# MPU-6050.net
KiCad netlist of a schematic drawn in Altium Designer
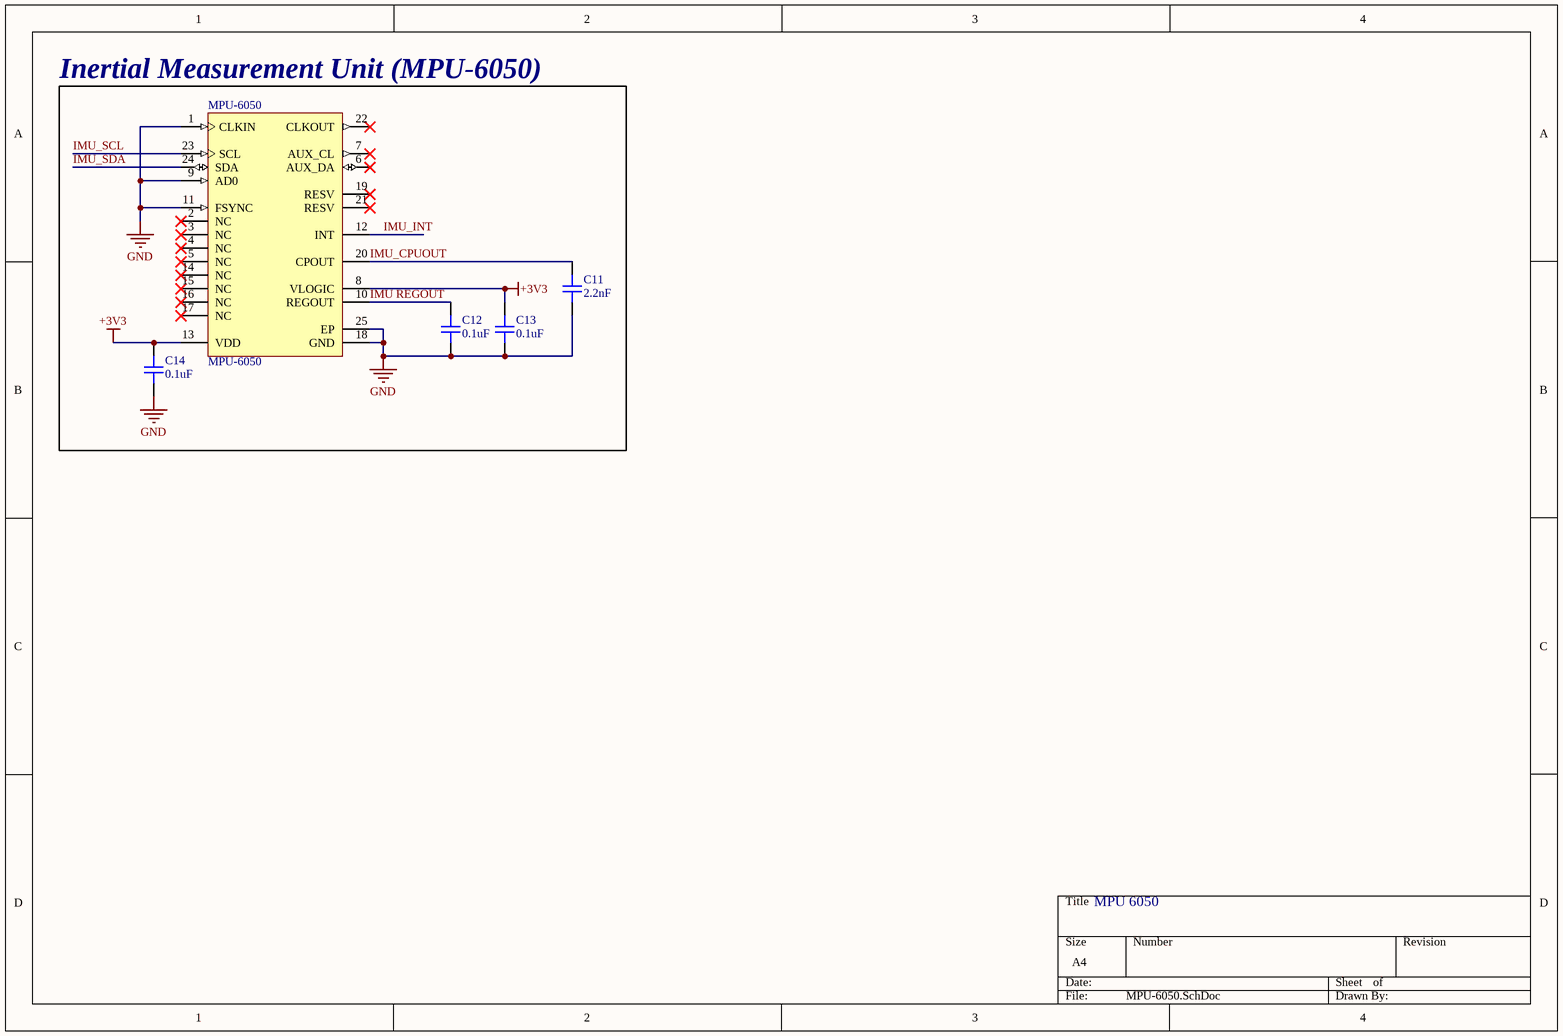
[diagram p0: MPU-6050.SchDoc]

(export (version "E")
  (design (tool "Eeschema 10.0.6"))
  (components
    (comp (ref "C11")
      (value "2.2nF")
      (footprint "CAP_0402")
      (description "Capacitor SMD 0402")
      (libsource (lib "Schematic-Lib-PhilsLab") (part "CAP_0402"))
    )
    (comp (ref "C12")
      (value "0.1uF")
      (footprint "CAP_0402")
      (description "Capacitor SMD 0402")
      (libsource (lib "Schematic-Lib-PhilsLab") (part "CAP_0402"))
    )
    (comp (ref "C13")
      (value "0.1uF")
      (footprint "CAP_0402")
      (description "Capacitor SMD 0402")
      (libsource (lib "Schematic-Lib-PhilsLab") (part "CAP_0402"))
    )
    (comp (ref "C14")
      (value "0.1uF")
      (footprint "CAP_0402")
      (description "Capacitor SMD 0402")
      (libsource (lib "Schematic-Lib-PhilsLab") (part "CAP_0402"))
    )
    (comp (ref "MPU-6050")
      (value "MPU-6050")
      (footprint "IS-QFN-24_V")
      (fields (field (name "MANUFACTURER") "InvenSense"))
      (libsource (lib "Altium Content Vault") (part "IS-MPU-6050-QFN-24"))
    )
  )
  (nets
    (net (code "1") (name "+3V3") (class "Default")
      (node (ref "C13") (pin "2") (pinfunction "2_2") (pintype "passive"))
      (node (ref "C14") (pin "2") (pinfunction "2_2") (pintype "passive"))
      (node (ref "MPU-6050") (pin "13") (pinfunction "VDD_13") (pintype "power_in"))
      (node (ref "MPU-6050") (pin "8") (pinfunction "VLOGIC_8") (pintype "power_in"))
    )
    (net (code "3") (name "/IMU REGOUT") (class "Default")
      (node (ref "C12") (pin "2") (pinfunction "2_2") (pintype "passive"))
      (node (ref "MPU-6050") (pin "10") (pinfunction "REGOUT_10") (pintype "passive"))
    )
    (net (code "4") (name "/IMU_CPUOUT") (class "Default")
      (node (ref "C11") (pin "2") (pinfunction "2_2") (pintype "passive"))
      (node (ref "MPU-6050") (pin "20") (pinfunction "CPOUT_20") (pintype "passive"))
    )
    (net (code "5") (name "/IMU_INT") (class "Default")
      (node (ref "MPU-6050") (pin "12") (pinfunction "INT_12") (pintype "open_collector"))
    )
    (net (code "6") (name "/IMU_SCL") (class "Default")
      (node (ref "MPU-6050") (pin "23") (pinfunction "SCL_23") (pintype "input"))
    )
    (net (code "7") (name "/IMU_SDA") (class "Default")
      (node (ref "MPU-6050") (pin "24") (pinfunction "SDA_24") (pintype "bidirectional"))
    )
    (net (code "8") (name "GND") (class "Default")
      (node (ref "C11") (pin "1") (pinfunction "1_1") (pintype "passive"))
      (node (ref "C12") (pin "1") (pinfunction "1_1") (pintype "passive"))
      (node (ref "C13") (pin "1") (pinfunction "1_1") (pintype "passive"))
      (node (ref "C14") (pin "1") (pinfunction "1_1") (pintype "passive"))
      (node (ref "MPU-6050") (pin "1") (pinfunction "CLKIN_1") (pintype "input"))
      (node (ref "MPU-6050") (pin "11") (pinfunction "FSYNC_11") (pintype "input"))
      (node (ref "MPU-6050") (pin "18") (pinfunction "GND_18") (pintype "power_in"))
      (node (ref "MPU-6050") (pin "25") (pinfunction "EP_25") (pintype "power_in"))
      (node (ref "MPU-6050") (pin "9") (pinfunction "AD0_9") (pintype "input"))
    )
    (net (code "9") (name "unconnected-(MPU-6050-AUX_CL-Pad7)") (class "Default")
      (node (ref "MPU-6050") (pin "7") (pinfunction "AUX_CL_7") (pintype "output+no_connect"))
    )
    (net (code "10") (name "unconnected-(MPU-6050-AUX_DA-Pad6)") (class "Default")
      (node (ref "MPU-6050") (pin "6") (pinfunction "AUX_DA_6") (pintype "bidirectional+no_connect"))
    )
    (net (code "11") (name "unconnected-(MPU-6050-CLKOUT-Pad22)") (class "Default")
      (node (ref "MPU-6050") (pin "22") (pinfunction "CLKOUT_22") (pintype "output+no_connect"))
    )
    (net (code "12") (name "unconnected-(MPU-6050-NC-Pad2)") (class "Default")
      (node (ref "MPU-6050") (pin "2") (pinfunction "NC_2") (pintype "passive+no_connect"))
    )
    (net (code "13") (name "unconnected-(MPU-6050-NC-Pad3)") (class "Default")
      (node (ref "MPU-6050") (pin "3") (pinfunction "NC_3") (pintype "passive+no_connect"))
    )
    (net (code "14") (name "unconnected-(MPU-6050-NC-Pad4)") (class "Default")
      (node (ref "MPU-6050") (pin "4") (pinfunction "NC_4") (pintype "passive+no_connect"))
    )
    (net (code "15") (name "unconnected-(MPU-6050-NC-Pad5)") (class "Default")
      (node (ref "MPU-6050") (pin "5") (pinfunction "NC_5") (pintype "passive+no_connect"))
    )
    (net (code "16") (name "unconnected-(MPU-6050-NC-Pad14)") (class "Default")
      (node (ref "MPU-6050") (pin "14") (pinfunction "NC_14") (pintype "passive+no_connect"))
    )
    (net (code "17") (name "unconnected-(MPU-6050-NC-Pad15)") (class "Default")
      (node (ref "MPU-6050") (pin "15") (pinfunction "NC_15") (pintype "passive+no_connect"))
    )
    (net (code "18") (name "unconnected-(MPU-6050-NC-Pad16)") (class "Default")
      (node (ref "MPU-6050") (pin "16") (pinfunction "NC_16") (pintype "passive+no_connect"))
    )
    (net (code "19") (name "unconnected-(MPU-6050-NC-Pad17)") (class "Default")
      (node (ref "MPU-6050") (pin "17") (pinfunction "NC_17") (pintype "passive+no_connect"))
    )
    (net (code "20") (name "unconnected-(MPU-6050-RESV-Pad19)") (class "Default")
      (node (ref "MPU-6050") (pin "19") (pinfunction "RESV_19") (pintype "passive+no_connect"))
    )
    (net (code "21") (name "unconnected-(MPU-6050-RESV-Pad21)") (class "Default")
      (node (ref "MPU-6050") (pin "21") (pinfunction "RESV_21") (pintype "passive+no_connect"))
    )
  )
)
